# HeadTracker.net
KiCad netlist of a schematic drawn in EAGLE
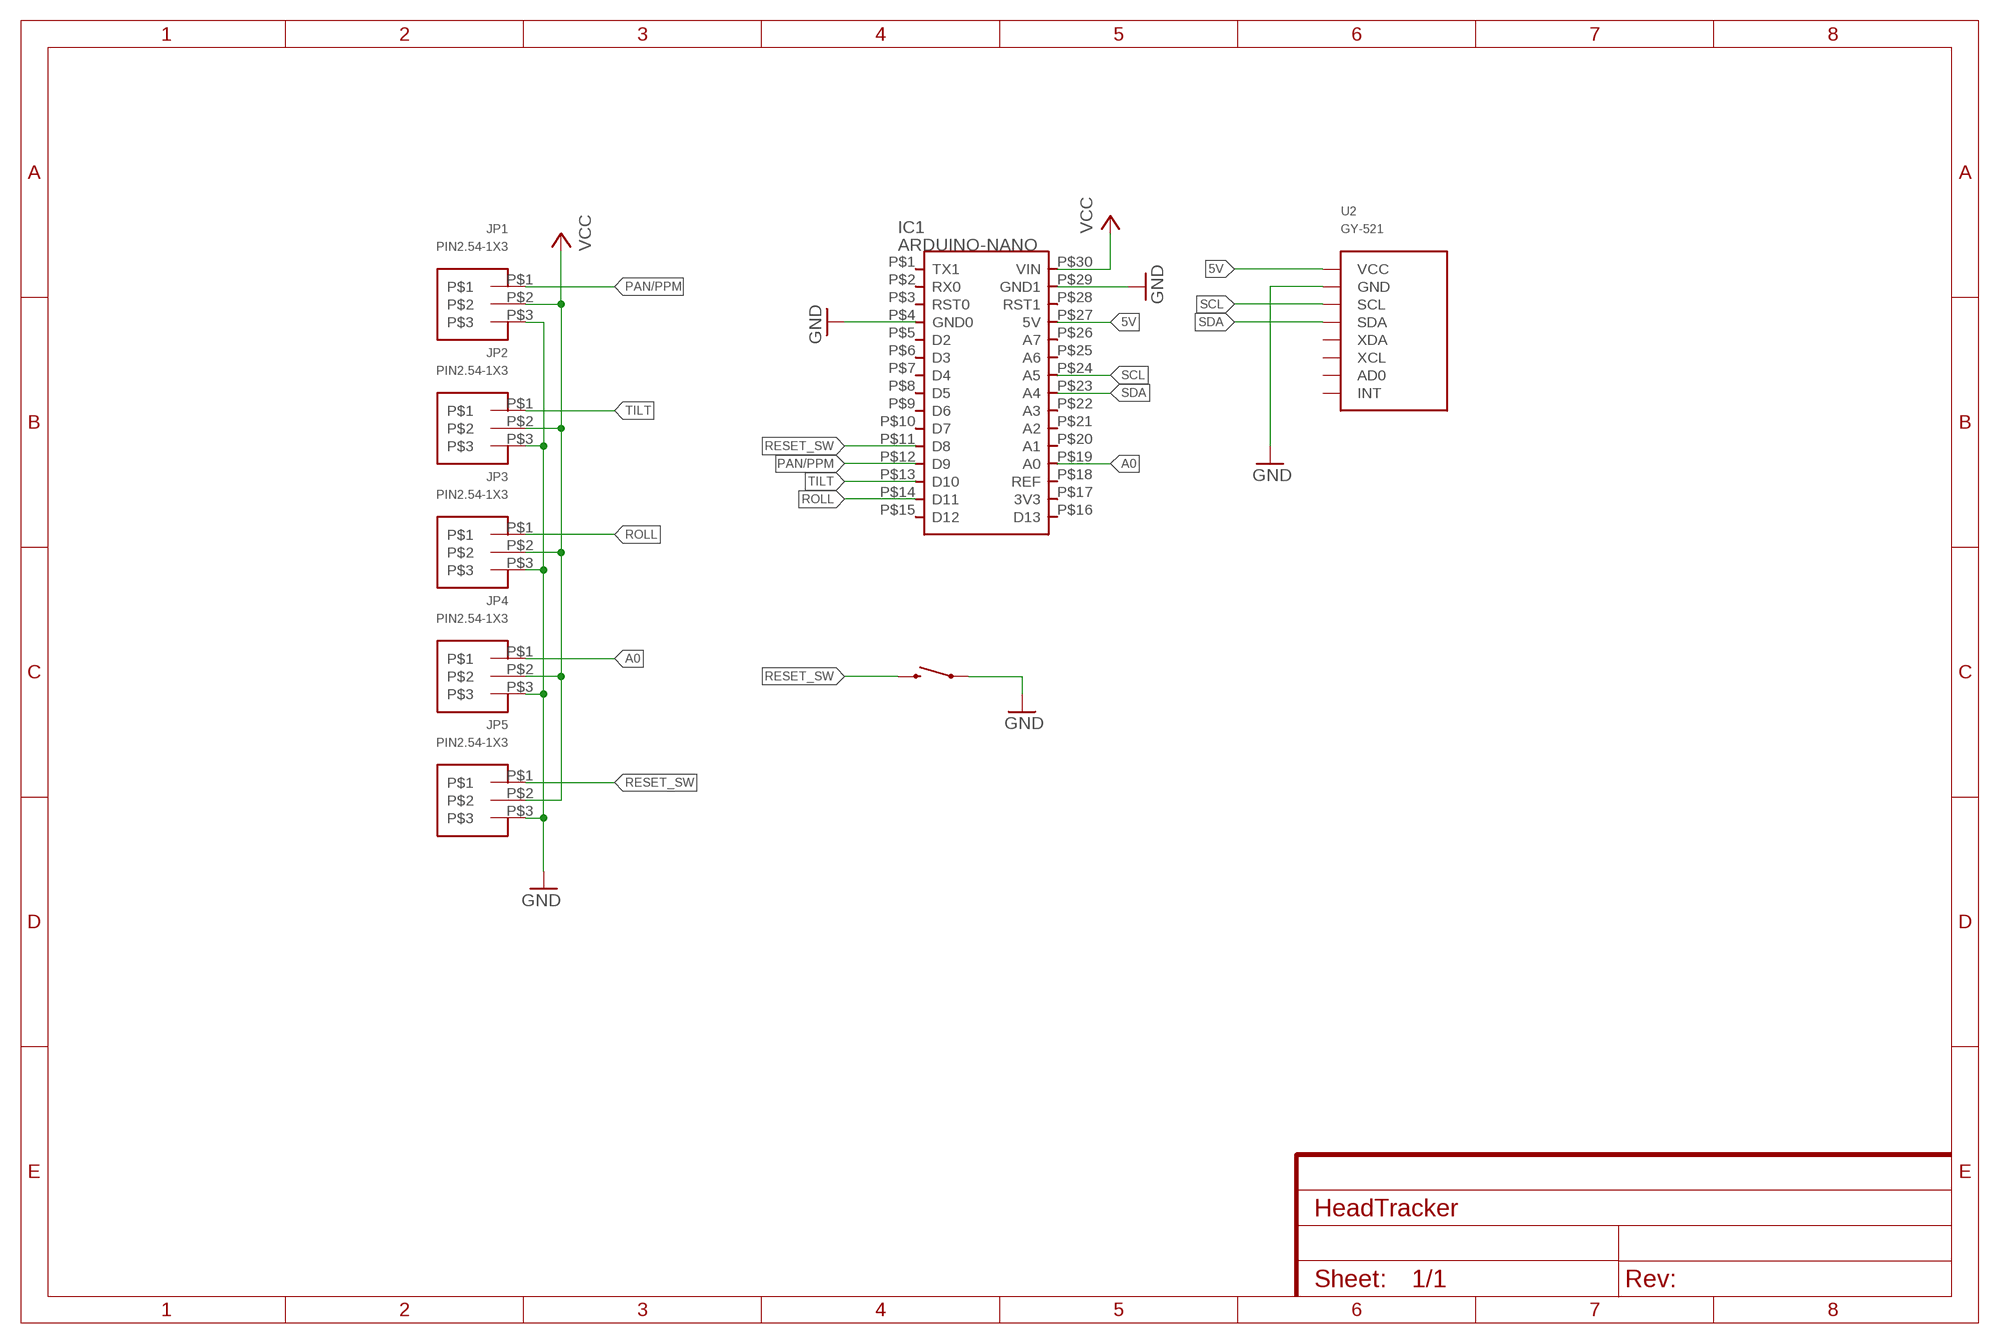
[diagram p0: schematic, sheet 1]

(export (version "E")
  (design (tool "Eeschema 10.0.6"))
  (components
    (comp (ref "IC1")
      (value "ARDUINO-NANO")
      (footprint "eagle-import:ARDUINO-NANO")
      (libsource (lib "eagle-import") (part "ARDUINO-NANO"))
    )
    (comp (ref "JP1")
      (value "PIN2.54-1X3")
      (footprint "eagle-import:PIN2.54-1X3")
      (libsource (lib "eagle-import") (part "PIN2.54-1X3"))
    )
    (comp (ref "JP2")
      (value "PIN2.54-1X3")
      (footprint "eagle-import:PIN2.54-1X3")
      (libsource (lib "eagle-import") (part "PIN2.54-1X3"))
    )
    (comp (ref "JP3")
      (value "PIN2.54-1X3")
      (footprint "eagle-import:PIN2.54-1X3")
      (libsource (lib "eagle-import") (part "PIN2.54-1X3"))
    )
    (comp (ref "JP4")
      (value "PIN2.54-1X3")
      (footprint "eagle-import:PIN2.54-1X3")
      (libsource (lib "eagle-import") (part "PIN2.54-1X3"))
    )
    (comp (ref "JP5")
      (value "PIN2.54-1X3")
      (footprint "eagle-import:PIN2.54-1X3")
      (libsource (lib "eagle-import") (part "PIN2.54-1X3"))
    )
    (comp (ref "S1")
      (value "SWITCH-MOMENTARY-2PTH")
      (footprint "eagle-import:TACTILE-PTH")
      (libsource (lib "eagle-import") (part "SWITCH-MOMENTARY-2PTH"))
    )
    (comp (ref "U2")
      (value "GY-521")
      (footprint "eagle-import:GY-521")
      (libsource (lib "eagle-import") (part "GY-521"))
    )
  )
  (nets
    (net (code "1") (name "5V") (class "Default")
      (node (ref "IC1") (pin "P$27") (pinfunction "5V_P$27") (pintype "bidirectional"))
      (node (ref "U2") (pin "P$1") (pinfunction "VCC_P$1") (pintype "bidirectional"))
    )
    (net (code "2") (name "A0") (class "Default")
      (node (ref "IC1") (pin "P$19") (pinfunction "A0_P$19") (pintype "bidirectional"))
      (node (ref "JP4") (pin "P$1") (pinfunction "P$1_P$1") (pintype "bidirectional"))
    )
    (net (code "3") (name "GND") (class "Default")
      (node (ref "IC1") (pin "P$29") (pinfunction "GND1_P$29") (pintype "bidirectional"))
      (node (ref "IC1") (pin "P$4") (pinfunction "GND0_P$4") (pintype "bidirectional"))
      (node (ref "JP1") (pin "P$3") (pinfunction "P$3_P$3") (pintype "bidirectional"))
      (node (ref "JP2") (pin "P$3") (pinfunction "P$3_P$3") (pintype "bidirectional"))
      (node (ref "JP3") (pin "P$3") (pinfunction "P$3_P$3") (pintype "bidirectional"))
      (node (ref "JP4") (pin "P$3") (pinfunction "P$3_P$3") (pintype "bidirectional"))
      (node (ref "JP5") (pin "P$3") (pinfunction "P$3_P$3") (pintype "bidirectional"))
      (node (ref "S1") (pin "1") (pinfunction "1_1") (pintype "passive"))
      (node (ref "U2") (pin "P$2") (pinfunction "GND_P$2") (pintype "bidirectional"))
    )
    (net (code "4") (name "PAN{slash}PPM") (class "Default")
      (node (ref "IC1") (pin "P$12") (pinfunction "D9_P$12") (pintype "bidirectional"))
      (node (ref "JP1") (pin "P$1") (pinfunction "P$1_P$1") (pintype "bidirectional"))
    )
    (net (code "5") (name "RESET_SW") (class "Default")
      (node (ref "IC1") (pin "P$11") (pinfunction "D8_P$11") (pintype "bidirectional"))
      (node (ref "JP5") (pin "P$1") (pinfunction "P$1_P$1") (pintype "bidirectional"))
      (node (ref "S1") (pin "3") (pinfunction "2_3") (pintype "passive"))
    )
    (net (code "6") (name "ROLL") (class "Default")
      (node (ref "IC1") (pin "P$14") (pinfunction "D11_P$14") (pintype "bidirectional"))
      (node (ref "JP3") (pin "P$1") (pinfunction "P$1_P$1") (pintype "bidirectional"))
    )
    (net (code "7") (name "SCL") (class "Default")
      (node (ref "IC1") (pin "P$24") (pinfunction "A5_P$24") (pintype "bidirectional"))
      (node (ref "U2") (pin "P$3") (pinfunction "SCL_P$3") (pintype "bidirectional"))
    )
    (net (code "8") (name "SDA") (class "Default")
      (node (ref "IC1") (pin "P$23") (pinfunction "A4_P$23") (pintype "bidirectional"))
      (node (ref "U2") (pin "P$4") (pinfunction "SDA_P$4") (pintype "bidirectional"))
    )
    (net (code "9") (name "TILT") (class "Default")
      (node (ref "IC1") (pin "P$13") (pinfunction "D10_P$13") (pintype "bidirectional"))
      (node (ref "JP2") (pin "P$1") (pinfunction "P$1_P$1") (pintype "bidirectional"))
    )
    (net (code "10") (name "VCC") (class "Default")
      (node (ref "IC1") (pin "P$30") (pinfunction "VIN_P$30") (pintype "bidirectional"))
      (node (ref "JP1") (pin "P$2") (pinfunction "P$2_P$2") (pintype "bidirectional"))
      (node (ref "JP2") (pin "P$2") (pinfunction "P$2_P$2") (pintype "bidirectional"))
      (node (ref "JP3") (pin "P$2") (pinfunction "P$2_P$2") (pintype "bidirectional"))
      (node (ref "JP4") (pin "P$2") (pinfunction "P$2_P$2") (pintype "bidirectional"))
      (node (ref "JP5") (pin "P$2") (pinfunction "P$2_P$2") (pintype "bidirectional"))
    )
    (net (code "11") (name "unconnected-(IC1-3V3-PadP$17)") (class "Default")
      (node (ref "IC1") (pin "P$17") (pinfunction "3V3_P$17") (pintype "bidirectional"))
    )
    (net (code "12") (name "unconnected-(IC1-A1-PadP$20)") (class "Default")
      (node (ref "IC1") (pin "P$20") (pinfunction "A1_P$20") (pintype "bidirectional"))
    )
    (net (code "13") (name "unconnected-(IC1-A2-PadP$21)") (class "Default")
      (node (ref "IC1") (pin "P$21") (pinfunction "A2_P$21") (pintype "bidirectional"))
    )
    (net (code "14") (name "unconnected-(IC1-A3-PadP$22)") (class "Default")
      (node (ref "IC1") (pin "P$22") (pinfunction "A3_P$22") (pintype "bidirectional"))
    )
    (net (code "15") (name "unconnected-(IC1-A6-PadP$25)") (class "Default")
      (node (ref "IC1") (pin "P$25") (pinfunction "A6_P$25") (pintype "bidirectional"))
    )
    (net (code "16") (name "unconnected-(IC1-A7-PadP$26)") (class "Default")
      (node (ref "IC1") (pin "P$26") (pinfunction "A7_P$26") (pintype "bidirectional"))
    )
    (net (code "17") (name "unconnected-(IC1-D2-PadP$5)") (class "Default")
      (node (ref "IC1") (pin "P$5") (pinfunction "D2_P$5") (pintype "bidirectional"))
    )
    (net (code "18") (name "unconnected-(IC1-D3-PadP$6)") (class "Default")
      (node (ref "IC1") (pin "P$6") (pinfunction "D3_P$6") (pintype "bidirectional"))
    )
    (net (code "19") (name "unconnected-(IC1-D4-PadP$7)") (class "Default")
      (node (ref "IC1") (pin "P$7") (pinfunction "D4_P$7") (pintype "bidirectional"))
    )
    (net (code "20") (name "unconnected-(IC1-D5-PadP$8)") (class "Default")
      (node (ref "IC1") (pin "P$8") (pinfunction "D5_P$8") (pintype "bidirectional"))
    )
    (net (code "21") (name "unconnected-(IC1-D6-PadP$9)") (class "Default")
      (node (ref "IC1") (pin "P$9") (pinfunction "D6_P$9") (pintype "bidirectional"))
    )
    (net (code "22") (name "unconnected-(IC1-D7-PadP$10)") (class "Default")
      (node (ref "IC1") (pin "P$10") (pinfunction "D7_P$10") (pintype "bidirectional"))
    )
    (net (code "23") (name "unconnected-(IC1-D12-PadP$15)") (class "Default")
      (node (ref "IC1") (pin "P$15") (pinfunction "D12_P$15") (pintype "bidirectional"))
    )
    (net (code "24") (name "unconnected-(IC1-D13-PadP$16)") (class "Default")
      (node (ref "IC1") (pin "P$16") (pinfunction "D13_P$16") (pintype "bidirectional"))
    )
    (net (code "25") (name "unconnected-(IC1-REF-PadP$18)") (class "Default")
      (node (ref "IC1") (pin "P$18") (pinfunction "REF_P$18") (pintype "bidirectional"))
    )
    (net (code "26") (name "unconnected-(IC1-RST0-PadP$3)") (class "Default")
      (node (ref "IC1") (pin "P$3") (pinfunction "RST0_P$3") (pintype "bidirectional"))
    )
    (net (code "27") (name "unconnected-(IC1-RST1-PadP$28)") (class "Default")
      (node (ref "IC1") (pin "P$28") (pinfunction "RST1_P$28") (pintype "bidirectional"))
    )
    (net (code "28") (name "unconnected-(IC1-RX0-PadP$2)") (class "Default")
      (node (ref "IC1") (pin "P$2") (pinfunction "RX0_P$2") (pintype "bidirectional"))
    )
    (net (code "29") (name "unconnected-(IC1-TX1-PadP$1)") (class "Default")
      (node (ref "IC1") (pin "P$1") (pinfunction "TX1_P$1") (pintype "bidirectional"))
    )
    (net (code "30") (name "unconnected-(U2-AD0-PadP$7)") (class "Default")
      (node (ref "U2") (pin "P$7") (pinfunction "AD0_P$7") (pintype "bidirectional"))
    )
    (net (code "31") (name "unconnected-(U2-INT-PadP$8)") (class "Default")
      (node (ref "U2") (pin "P$8") (pinfunction "INT_P$8") (pintype "bidirectional"))
    )
    (net (code "32") (name "unconnected-(U2-XCL-PadP$6)") (class "Default")
      (node (ref "U2") (pin "P$6") (pinfunction "XCL_P$6") (pintype "bidirectional"))
    )
    (net (code "33") (name "unconnected-(U2-XDA-PadP$5)") (class "Default")
      (node (ref "U2") (pin "P$5") (pinfunction "XDA_P$5") (pintype "bidirectional"))
    )
  )
)
